# PS.net
KiCad netlist of a schematic drawn in EAGLE
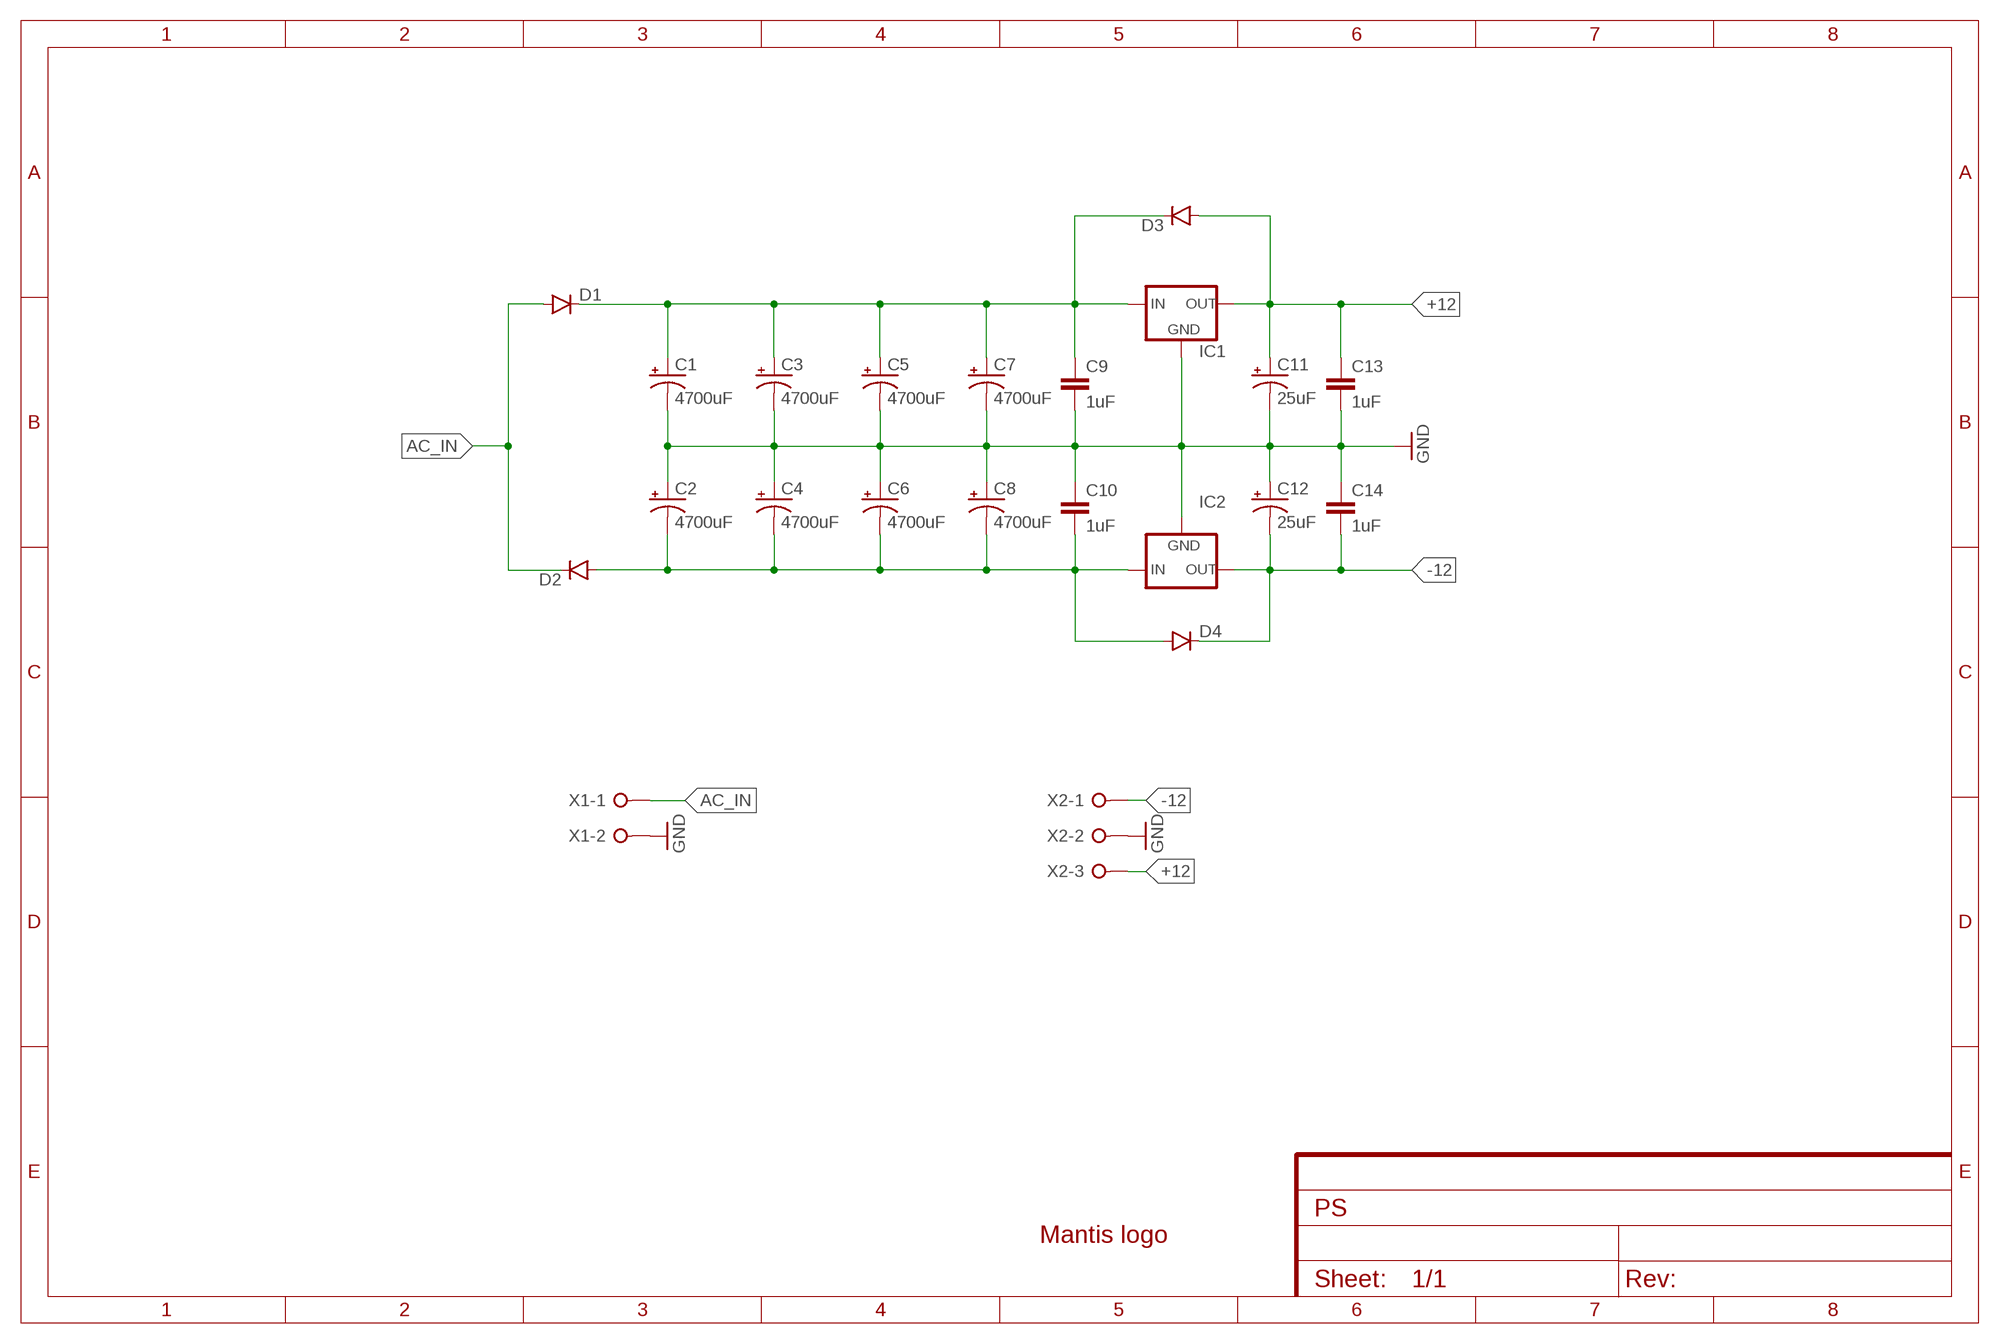
[diagram p0: schematic, sheet 1]

(export (version "E")
  (design (tool "Eeschema 10.0.6"))
  (components
    (comp (ref "C1")
      (value "4700uF")
      (footprint "eagle-import:CPOL-RADIAL-1000UF-63V")
      (libsource (lib "eagle-import") (part "CAP_POLPTH3"))
    )
    (comp (ref "C2")
      (value "4700uF")
      (footprint "eagle-import:CPOL-RADIAL-1000UF-63V")
      (libsource (lib "eagle-import") (part "CAP_POLPTH3"))
    )
    (comp (ref "C3")
      (value "4700uF")
      (footprint "eagle-import:CPOL-RADIAL-1000UF-63V")
      (libsource (lib "eagle-import") (part "CAP_POLPTH3"))
    )
    (comp (ref "C4")
      (value "4700uF")
      (footprint "eagle-import:CPOL-RADIAL-1000UF-63V")
      (libsource (lib "eagle-import") (part "CAP_POLPTH3"))
    )
    (comp (ref "C5")
      (value "4700uF")
      (footprint "eagle-import:CPOL-RADIAL-1000UF-63V")
      (libsource (lib "eagle-import") (part "CAP_POLPTH3"))
    )
    (comp (ref "C6")
      (value "4700uF")
      (footprint "eagle-import:CPOL-RADIAL-1000UF-63V")
      (libsource (lib "eagle-import") (part "CAP_POLPTH3"))
    )
    (comp (ref "C7")
      (value "4700uF")
      (footprint "eagle-import:CPOL-RADIAL-1000UF-63V")
      (libsource (lib "eagle-import") (part "CAP_POLPTH3"))
    )
    (comp (ref "C8")
      (value "4700uF")
      (footprint "eagle-import:CPOL-RADIAL-1000UF-63V")
      (libsource (lib "eagle-import") (part "CAP_POLPTH3"))
    )
    (comp (ref "C9")
      (value "1uF")
      (footprint "eagle-import:CAP-PTH-SMALL")
      (libsource (lib "eagle-import") (part "CAPPTH"))
    )
    (comp (ref "C10")
      (value "1uF")
      (footprint "eagle-import:CAP-PTH-SMALL")
      (libsource (lib "eagle-import") (part "CAPPTH"))
    )
    (comp (ref "C11")
      (value "25uF")
      (footprint "eagle-import:CPOL-RADIAL-10UF-25V")
      (libsource (lib "eagle-import") (part "CAP_POLPTH2"))
    )
    (comp (ref "C12")
      (value "25uF")
      (footprint "eagle-import:CPOL-RADIAL-10UF-25V")
      (libsource (lib "eagle-import") (part "CAP_POLPTH2"))
    )
    (comp (ref "C13")
      (value "1uF")
      (footprint "eagle-import:CAP-PTH-SMALL")
      (libsource (lib "eagle-import") (part "CAPPTH"))
    )
    (comp (ref "C14")
      (value "1uF")
      (footprint "eagle-import:CAP-PTH-SMALL")
      (libsource (lib "eagle-import") (part "CAPPTH"))
    )
    (comp (ref "D1")
      (value "DIODEPTH")
      (footprint "eagle-import:DIODE-1N4001")
      (libsource (lib "eagle-import") (part "DIODEPTH"))
    )
    (comp (ref "D2")
      (value "DIODEPTH")
      (footprint "eagle-import:DIODE-1N4001")
      (libsource (lib "eagle-import") (part "DIODEPTH"))
    )
    (comp (ref "D3")
      (value "DIODEPTH")
      (footprint "eagle-import:DIODE-1N4001")
      (libsource (lib "eagle-import") (part "DIODEPTH"))
    )
    (comp (ref "D4")
      (value "DIODEPTH")
      (footprint "eagle-import:DIODE-1N4001")
      (libsource (lib "eagle-import") (part "DIODEPTH"))
    )
    (comp (ref "IC1")
      (value "78XXL")
      (footprint "eagle-import:78XXL")
      (libsource (lib "eagle-import") (part "78XXL"))
    )
    (comp (ref "IC2")
      (value "79XXL")
      (footprint "eagle-import:79XXL")
      (libsource (lib "eagle-import") (part "79XXL"))
    )
    (comp (ref "LOGO1")
      (value "LOGO-MANTIS")
      (footprint "eagle-import:LOGO-MANTIS")
      (libsource (lib "eagle-import") (part "LOGO-MANTIS"))
    )
    (comp (ref "X1")
      (value "W237-02P")
      (footprint "eagle-import:W237-132")
      (libsource (lib "eagle-import") (part "W237-02P"))
    )
    (comp (ref "X2")
      (value "W237-3E")
      (footprint "eagle-import:W237-3E")
      (libsource (lib "eagle-import") (part "W237-3E"))
    )
  )
  (nets
    (net (code "1") (name "+12") (class "Default")
      (node (ref "C11") (pin "1") (pinfunction "+_1") (pintype "passive"))
      (node (ref "C13") (pin "1") (pinfunction "1_1") (pintype "passive"))
      (node (ref "D3") (pin "A") (pinfunction "A_A") (pintype "passive"))
      (node (ref "IC1") (pin "OUT") (pinfunction "OUT_OUT") (pintype "passive"))
      (node (ref "X2") (pin "3") (pinfunction "KL_3") (pintype "passive"))
    )
    (net (code "2") (name "-12") (class "Default")
      (node (ref "C12") (pin "2") (pinfunction "-_2") (pintype "passive"))
      (node (ref "C14") (pin "2") (pinfunction "2_2") (pintype "passive"))
      (node (ref "D4") (pin "C") (pinfunction "C_C") (pintype "passive"))
      (node (ref "IC2") (pin "OUT") (pinfunction "OUT_OUT") (pintype "passive"))
      (node (ref "X2") (pin "1") (pinfunction "KL_1") (pintype "passive"))
    )
    (net (code "3") (name "AC_IN") (class "Default")
      (node (ref "D1") (pin "A") (pinfunction "A_A") (pintype "passive"))
      (node (ref "D2") (pin "C") (pinfunction "C_C") (pintype "passive"))
      (node (ref "X1") (pin "1") (pinfunction "KL_1") (pintype "passive"))
    )
    (net (code "4") (name "GND") (class "Default")
      (node (ref "C1") (pin "2") (pinfunction "-_2") (pintype "passive"))
      (node (ref "C10") (pin "1") (pinfunction "1_1") (pintype "passive"))
      (node (ref "C11") (pin "2") (pinfunction "-_2") (pintype "passive"))
      (node (ref "C12") (pin "1") (pinfunction "+_1") (pintype "passive"))
      (node (ref "C13") (pin "2") (pinfunction "2_2") (pintype "passive"))
      (node (ref "C14") (pin "1") (pinfunction "1_1") (pintype "passive"))
      (node (ref "C2") (pin "1") (pinfunction "+_1") (pintype "passive"))
      (node (ref "C3") (pin "2") (pinfunction "-_2") (pintype "passive"))
      (node (ref "C4") (pin "1") (pinfunction "+_1") (pintype "passive"))
      (node (ref "C5") (pin "2") (pinfunction "-_2") (pintype "passive"))
      (node (ref "C6") (pin "1") (pinfunction "+_1") (pintype "passive"))
      (node (ref "C7") (pin "2") (pinfunction "-_2") (pintype "passive"))
      (node (ref "C8") (pin "1") (pinfunction "+_1") (pintype "passive"))
      (node (ref "C9") (pin "2") (pinfunction "2_2") (pintype "passive"))
      (node (ref "IC1") (pin "GND") (pinfunction "GND_GND") (pintype "input"))
      (node (ref "IC2") (pin "GND") (pinfunction "GND_GND") (pintype "input"))
      (node (ref "X1") (pin "2") (pinfunction "KL_2") (pintype "passive"))
      (node (ref "X2") (pin "2") (pinfunction "KL_2") (pintype "passive"))
    )
    (net (code "5") (name "Net-(C1-+)") (class "Default")
      (node (ref "C1") (pin "1") (pinfunction "+_1") (pintype "passive"))
      (node (ref "C3") (pin "1") (pinfunction "+_1") (pintype "passive"))
      (node (ref "C5") (pin "1") (pinfunction "+_1") (pintype "passive"))
      (node (ref "C7") (pin "1") (pinfunction "+_1") (pintype "passive"))
      (node (ref "C9") (pin "1") (pinfunction "1_1") (pintype "passive"))
      (node (ref "D1") (pin "C") (pinfunction "C_C") (pintype "passive"))
      (node (ref "D3") (pin "C") (pinfunction "C_C") (pintype "passive"))
      (node (ref "IC1") (pin "IN") (pinfunction "IN_IN") (pintype "input"))
    )
    (net (code "6") (name "Net-(C2--)") (class "Default")
      (node (ref "C10") (pin "2") (pinfunction "2_2") (pintype "passive"))
      (node (ref "C2") (pin "2") (pinfunction "-_2") (pintype "passive"))
      (node (ref "C4") (pin "2") (pinfunction "-_2") (pintype "passive"))
      (node (ref "C6") (pin "2") (pinfunction "-_2") (pintype "passive"))
      (node (ref "C8") (pin "2") (pinfunction "-_2") (pintype "passive"))
      (node (ref "D2") (pin "A") (pinfunction "A_A") (pintype "passive"))
      (node (ref "D4") (pin "A") (pinfunction "A_A") (pintype "passive"))
      (node (ref "IC2") (pin "IN") (pinfunction "IN_IN") (pintype "input"))
    )
  )
)
